# persephone_B_v1.net
KiCad netlist of a schematic drawn in EAGLE
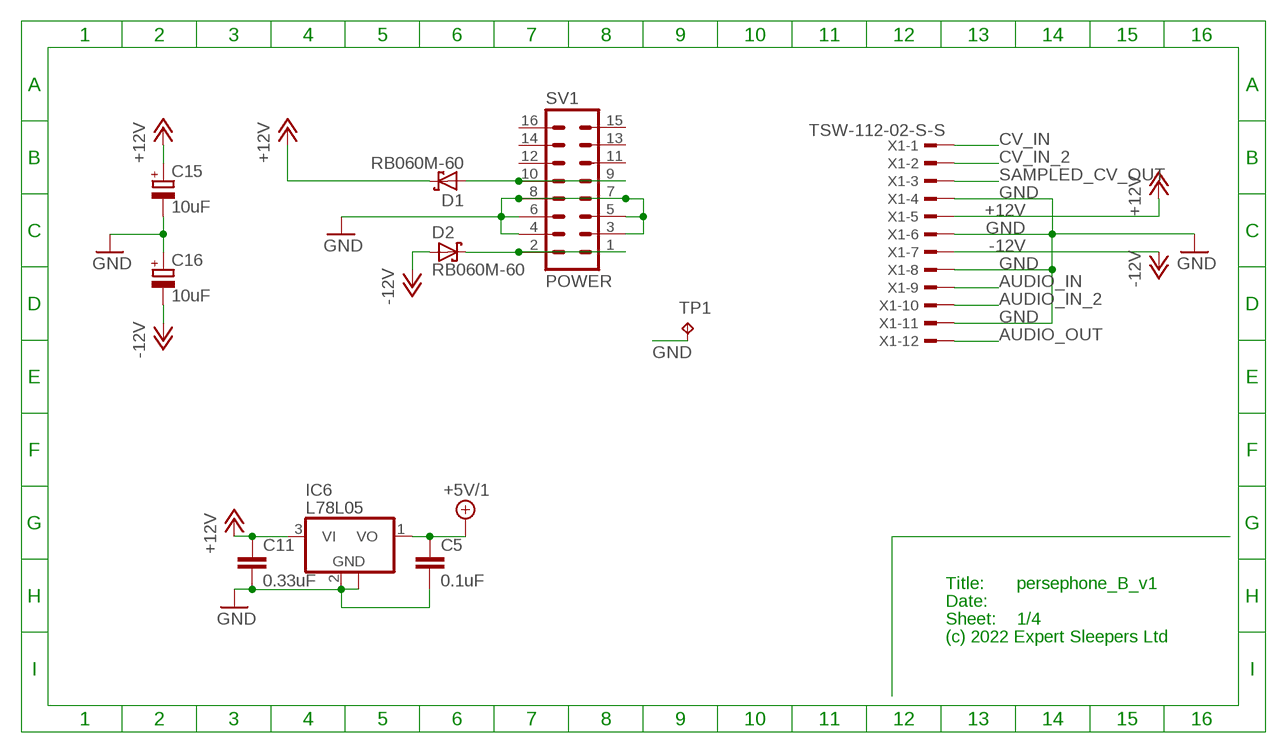
[diagram p0: schematic, sheet 1]
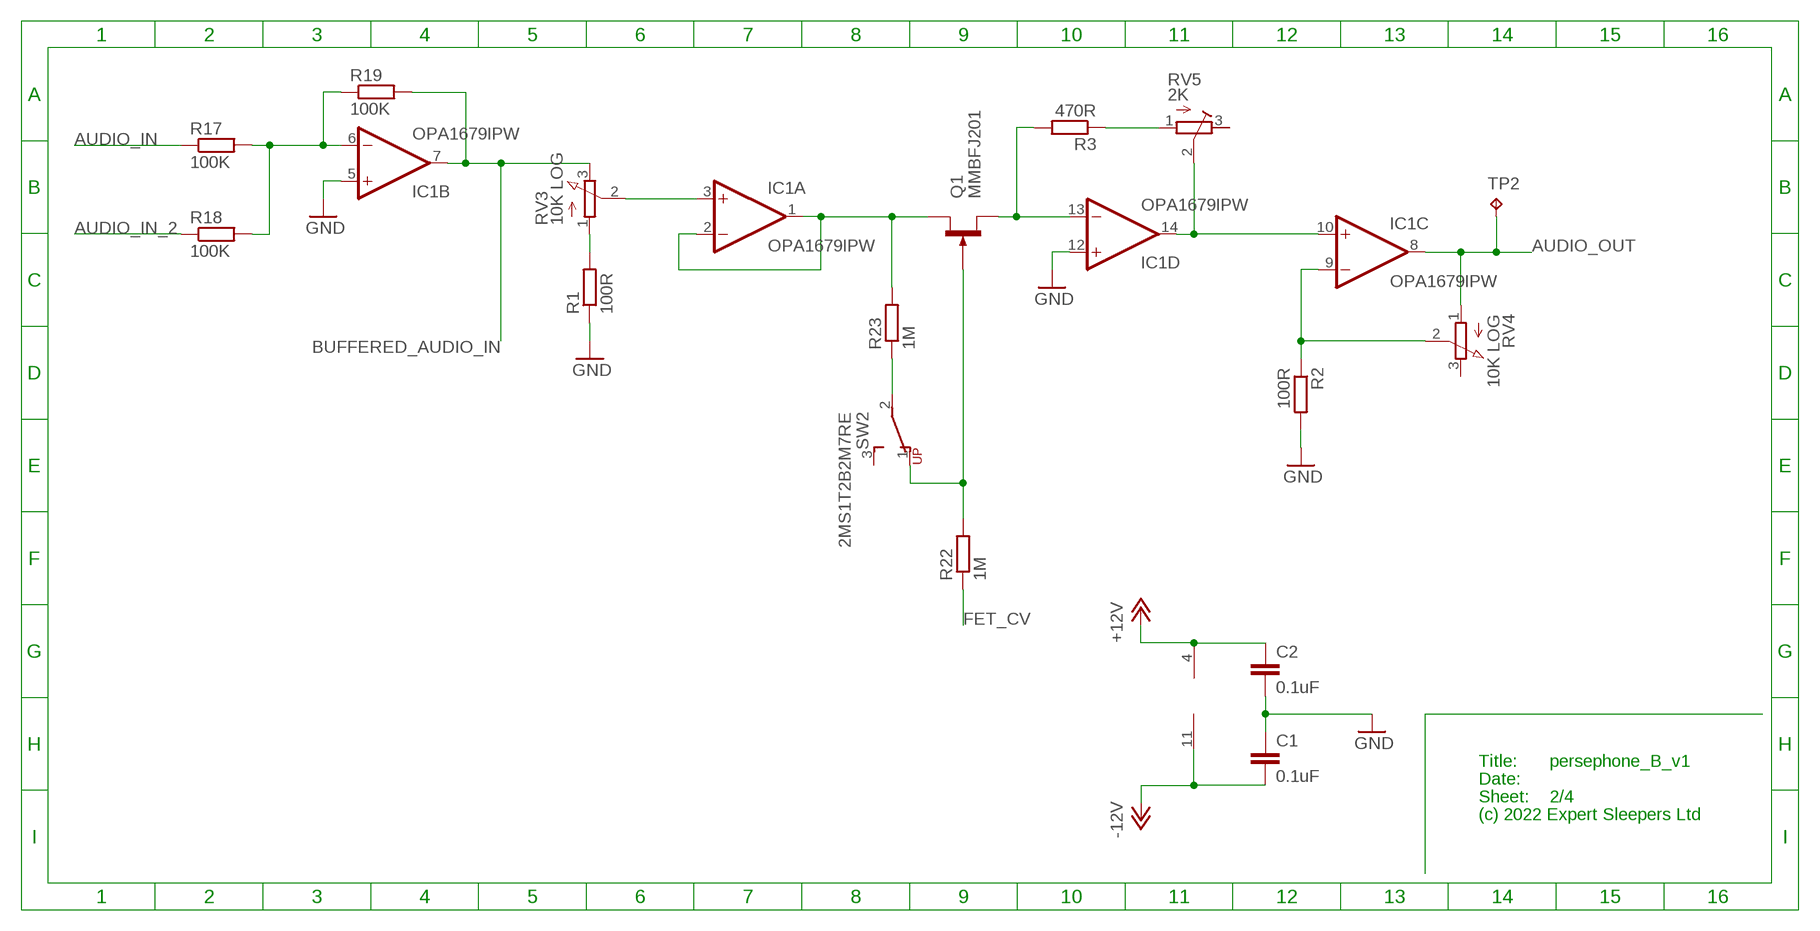
[diagram p1: schematic, sheet 2]
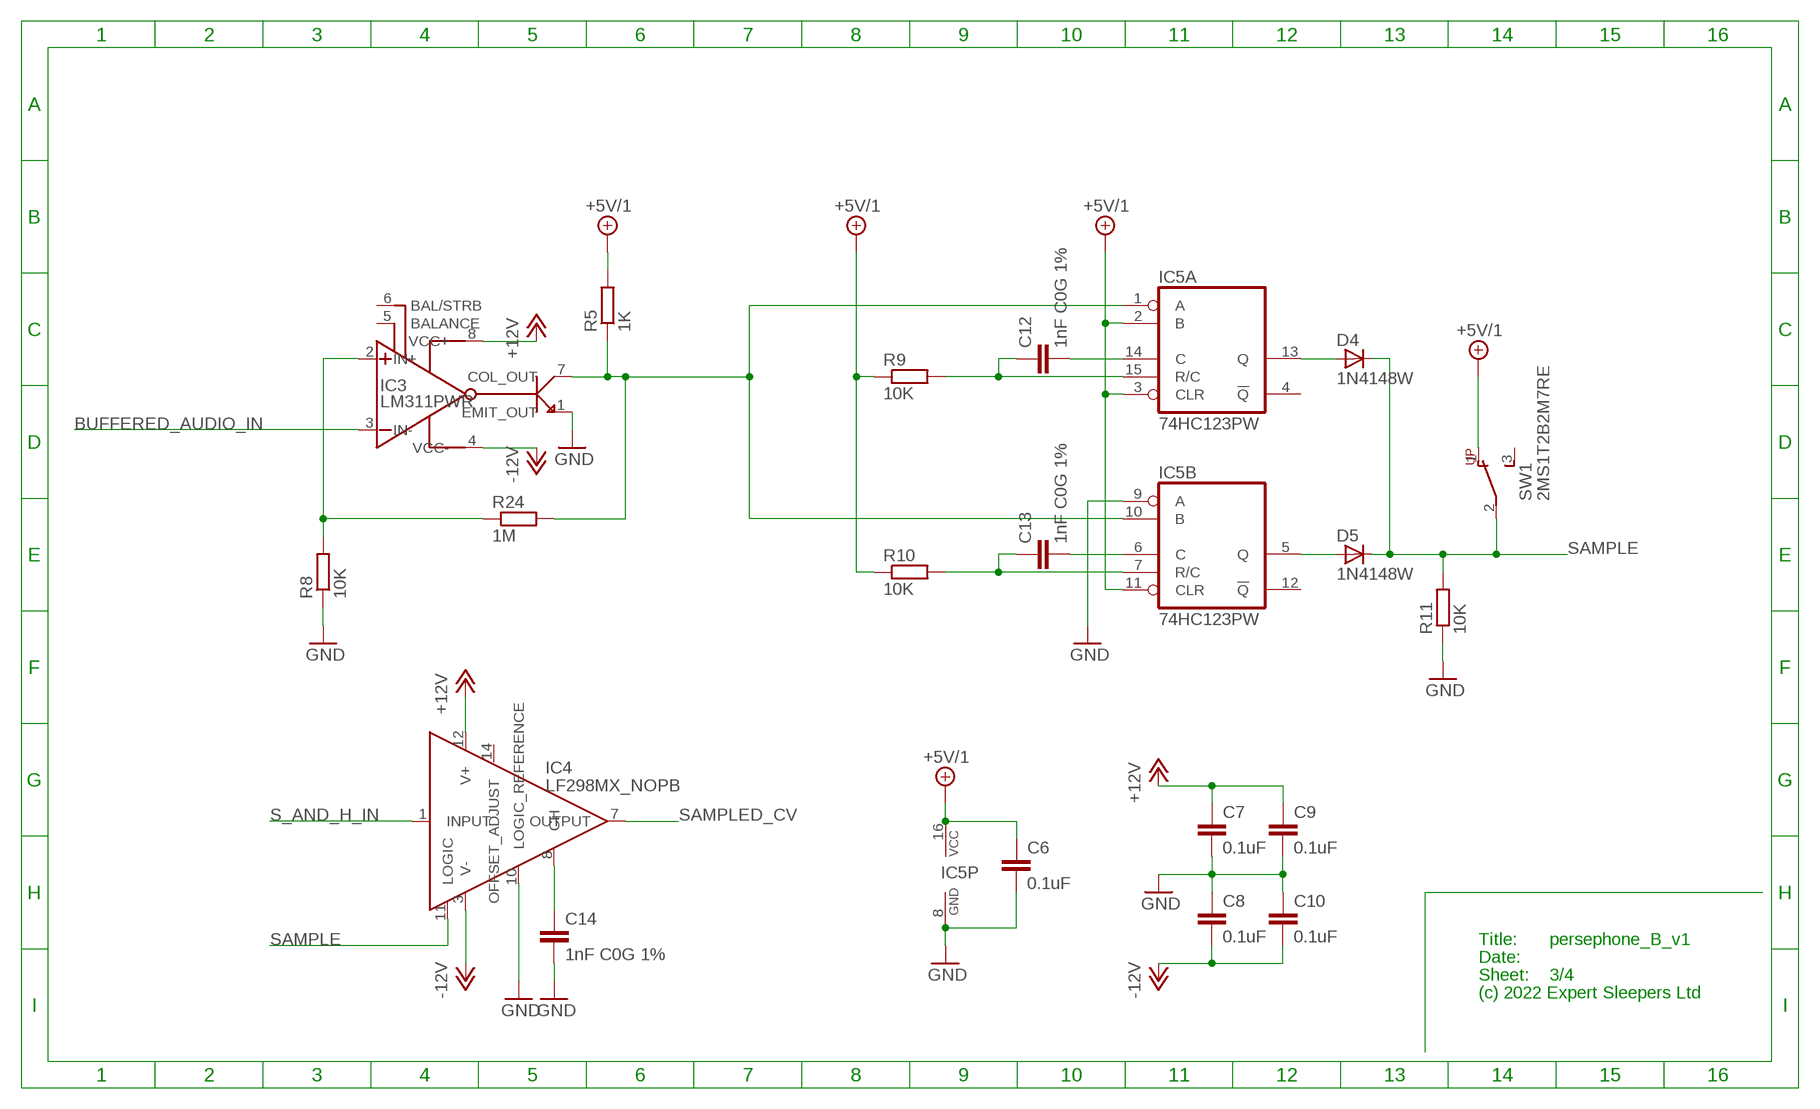
[diagram p2: schematic, sheet 3]
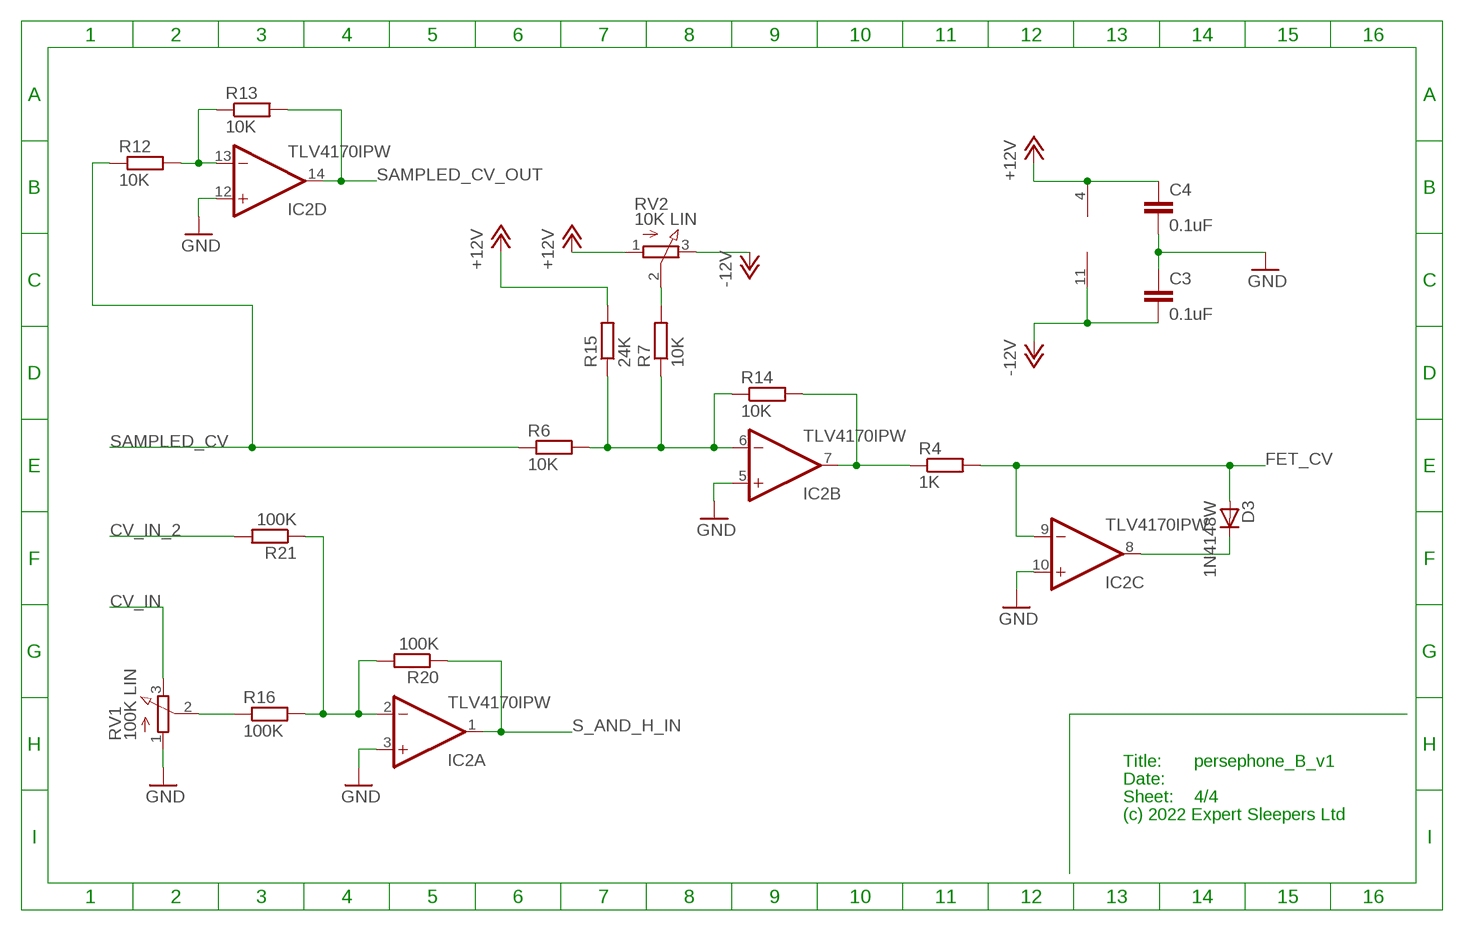
[diagram p3: schematic, sheet 4]

(export (version "E")
  (design (tool "Eeschema 10.0.6"))
  (components
    (comp (ref "C5")
      (value "0.1uF")
      (footprint "eagle-import:C0402")
      (libsource (lib "eagle-import") (part "C-EUC0402"))
    )
    (comp (ref "C11")
      (value "0.33uF")
      (footprint "eagle-import:C0805")
      (libsource (lib "eagle-import") (part "C-EUC0805"))
    )
    (comp (ref "C15")
      (value "10uF")
      (footprint "eagle-import:UD-4X5,8_NICHICON")
      (libsource (lib "eagle-import") (part "CPOL-EUUD-4X5,8"))
    )
    (comp (ref "C16")
      (value "10uF")
      (footprint "eagle-import:UD-4X5,8_NICHICON")
      (libsource (lib "eagle-import") (part "CPOL-EUUD-4X5,8"))
    )
    (comp (ref "D1")
      (value "RB060M-60")
      (footprint "eagle-import:SOD123FL")
      (libsource (lib "eagle-import") (part "RB060M-60"))
    )
    (comp (ref "D2")
      (value "RB060M-60")
      (footprint "eagle-import:SOD123FL")
      (libsource (lib "eagle-import") (part "RB060M-60"))
    )
    (comp (ref "IC6")
      (value "L78L05")
      (footprint "eagle-import:SOT89")
      (libsource (lib "eagle-import") (part "78LF05"))
    )
    (comp (ref "SV1")
      (value "POWER")
      (footprint "eagle-import:ML16")
      (libsource (lib "eagle-import") (part "ML16"))
    )
    (comp (ref "TP1")
      (value "RA2")
      (footprint "eagle-import:P1-13")
      (libsource (lib "eagle-import") (part "TPPAD1-13"))
    )
    (comp (ref "X1")
      (value "TSW-112-02-S-S")
      (footprint "eagle-import:TSW-112-02-S-S")
      (libsource (lib "eagle-import") (part "TSW-112-02-S-S"))
    )
    (comp (ref "C1")
      (value "0.1uF")
      (footprint "eagle-import:C0402")
      (libsource (lib "eagle-import") (part "C-EUC0402"))
    )
    (comp (ref "C2")
      (value "0.1uF")
      (footprint "eagle-import:C0402")
      (libsource (lib "eagle-import") (part "C-EUC0402"))
    )
    (comp (ref "IC1")
      (value "OPA1679IPW")
      (footprint "eagle-import:PW_R-PDSO-G14")
      (libsource (lib "eagle-import") (part "TL074PW"))
    )
    (comp (ref "Q1")
      (value "MMBFJ201")
      (footprint "eagle-import:SOT23")
      (libsource (lib "eagle-import") (part "MMBFJ3"))
    )
    (comp (ref "R1")
      (value "100R")
      (footprint "eagle-import:R0603")
      (libsource (lib "eagle-import") (part "R-EU_R0603"))
    )
    (comp (ref "R2")
      (value "100R")
      (footprint "eagle-import:R0603")
      (libsource (lib "eagle-import") (part "R-EU_R0603"))
    )
    (comp (ref "R3")
      (value "470R")
      (footprint "eagle-import:R0603")
      (libsource (lib "eagle-import") (part "R-EU_R0603"))
    )
    (comp (ref "R17")
      (value "100K")
      (footprint "eagle-import:R0603")
      (libsource (lib "eagle-import") (part "R-EU_R0603"))
    )
    (comp (ref "R18")
      (value "100K")
      (footprint "eagle-import:R0603")
      (libsource (lib "eagle-import") (part "R-EU_R0603"))
    )
    (comp (ref "R19")
      (value "100K")
      (footprint "eagle-import:R0603")
      (libsource (lib "eagle-import") (part "R-EU_R0603"))
    )
    (comp (ref "R22")
      (value "1M")
      (footprint "eagle-import:R0603")
      (libsource (lib "eagle-import") (part "R-EU_R0603"))
    )
    (comp (ref "R23")
      (value "1M")
      (footprint "eagle-import:R0603")
      (libsource (lib "eagle-import") (part "R-EU_R0603"))
    )
    (comp (ref "RV3")
      (value "10K LOG")
      (footprint "eagle-import:RD1610NOA0X")
      (libsource (lib "eagle-import") (part "RD1610NOA0X"))
    )
    (comp (ref "RV4")
      (value "10K LOG")
      (footprint "eagle-import:RD1610NOA0X")
      (libsource (lib "eagle-import") (part "RD1610NOA0X"))
    )
    (comp (ref "RV5")
      (value "2K")
      (footprint "eagle-import:TC33X")
      (libsource (lib "eagle-import") (part "TC33X"))
    )
    (comp (ref "SW2")
      (value "2MS1T2B2M7RE")
      (footprint "eagle-import:2MS1T2B2M7RE")
      (libsource (lib "eagle-import") (part "2MS1T2B2M7RE"))
    )
    (comp (ref "TP2")
      (value "RA2")
      (footprint "eagle-import:P1-13")
      (libsource (lib "eagle-import") (part "TPPAD1-13"))
    )
    (comp (ref "C6")
      (value "0.1uF")
      (footprint "eagle-import:C0402")
      (libsource (lib "eagle-import") (part "C-EUC0402"))
    )
    (comp (ref "C7")
      (value "0.1uF")
      (footprint "eagle-import:C0402")
      (libsource (lib "eagle-import") (part "C-EUC0402"))
    )
    (comp (ref "C8")
      (value "0.1uF")
      (footprint "eagle-import:C0402")
      (libsource (lib "eagle-import") (part "C-EUC0402"))
    )
    (comp (ref "C9")
      (value "0.1uF")
      (footprint "eagle-import:C0402")
      (libsource (lib "eagle-import") (part "C-EUC0402"))
    )
    (comp (ref "C10")
      (value "0.1uF")
      (footprint "eagle-import:C0402")
      (libsource (lib "eagle-import") (part "C-EUC0402"))
    )
    (comp (ref "C12")
      (value "1nF C0G 1%")
      (footprint "eagle-import:C0603")
      (libsource (lib "eagle-import") (part "C-EUC0603"))
    )
    (comp (ref "C13")
      (value "1nF C0G 1%")
      (footprint "eagle-import:C0603")
      (libsource (lib "eagle-import") (part "C-EUC0603"))
    )
    (comp (ref "C14")
      (value "1nF C0G 1%")
      (footprint "eagle-import:C0603")
      (libsource (lib "eagle-import") (part "C-EUC0603"))
    )
    (comp (ref "D4")
      (value "1N4148W")
      (footprint "eagle-import:SOD123")
      (libsource (lib "eagle-import") (part "D-SOD123"))
    )
    (comp (ref "D5")
      (value "1N4148W")
      (footprint "eagle-import:SOD123")
      (libsource (lib "eagle-import") (part "D-SOD123"))
    )
    (comp (ref "IC3")
      (value "LM311PWR")
      (footprint "eagle-import:SOP65P640X120-8N")
      (fields (field (name "MOUSER_PART_NUMBER") "595-LM311PWR"))
      (libsource (lib "eagle-import") (part "LM311PWR"))
    )
    (comp (ref "IC4")
      (value "LF298MX_NOPB")
      (footprint "eagle-import:SOIC127P600X175-14N")
      (fields
        (field (name "ARROW_PART_NUMBER") "LF298MX/NOPB")
        (field (name "MOUSER_PART_NUMBER") "926-LF298MX/NOPB")
      )
      (libsource (lib "eagle-import") (part "LF298MX_NOPB"))
    )
    (comp (ref "IC5")
      (value "74HC123PW")
      (footprint "eagle-import:PW_R-PDSO-G16")
      (libsource (lib "eagle-import") (part "74123PWHC"))
    )
    (comp (ref "R5")
      (value "1K")
      (footprint "eagle-import:R0603")
      (libsource (lib "eagle-import") (part "R-EU_R0603"))
    )
    (comp (ref "R8")
      (value "10K")
      (footprint "eagle-import:R0603")
      (libsource (lib "eagle-import") (part "R-EU_R0603"))
    )
    (comp (ref "R9")
      (value "10K")
      (footprint "eagle-import:R0603")
      (libsource (lib "eagle-import") (part "R-EU_R0603"))
    )
    (comp (ref "R10")
      (value "10K")
      (footprint "eagle-import:R0603")
      (libsource (lib "eagle-import") (part "R-EU_R0603"))
    )
    (comp (ref "R11")
      (value "10K")
      (footprint "eagle-import:R0603")
      (libsource (lib "eagle-import") (part "R-EU_R0603"))
    )
    (comp (ref "R24")
      (value "1M")
      (footprint "eagle-import:R0603")
      (libsource (lib "eagle-import") (part "R-EU_R0603"))
    )
    (comp (ref "SW1")
      (value "2MS1T2B2M7RE")
      (footprint "eagle-import:2MS1T2B2M7RE")
      (libsource (lib "eagle-import") (part "2MS1T2B2M7RE"))
    )
    (comp (ref "C3")
      (value "0.1uF")
      (footprint "eagle-import:C0402")
      (libsource (lib "eagle-import") (part "C-EUC0402"))
    )
    (comp (ref "C4")
      (value "0.1uF")
      (footprint "eagle-import:C0402")
      (libsource (lib "eagle-import") (part "C-EUC0402"))
    )
    (comp (ref "D3")
      (value "1N4148W")
      (footprint "eagle-import:SOD123")
      (libsource (lib "eagle-import") (part "D-SOD123"))
    )
    (comp (ref "IC2")
      (value "TLV4170IPW")
      (footprint "eagle-import:PW_R-PDSO-G14")
      (libsource (lib "eagle-import") (part "TL074PW"))
    )
    (comp (ref "R4")
      (value "1K")
      (footprint "eagle-import:R0603")
      (libsource (lib "eagle-import") (part "R-EU_R0603"))
    )
    (comp (ref "R6")
      (value "10K")
      (footprint "eagle-import:R0603")
      (libsource (lib "eagle-import") (part "R-EU_R0603"))
    )
    (comp (ref "R7")
      (value "10K")
      (footprint "eagle-import:R0603")
      (libsource (lib "eagle-import") (part "R-EU_R0603"))
    )
    (comp (ref "R12")
      (value "10K")
      (footprint "eagle-import:R0603")
      (libsource (lib "eagle-import") (part "R-EU_R0603"))
    )
    (comp (ref "R13")
      (value "10K")
      (footprint "eagle-import:R0603")
      (libsource (lib "eagle-import") (part "R-EU_R0603"))
    )
    (comp (ref "R14")
      (value "10K")
      (footprint "eagle-import:R0603")
      (libsource (lib "eagle-import") (part "R-EU_R0603"))
    )
    (comp (ref "R15")
      (value "24K")
      (footprint "eagle-import:R0603")
      (libsource (lib "eagle-import") (part "R-EU_R0603"))
    )
    (comp (ref "R16")
      (value "100K")
      (footprint "eagle-import:R0603")
      (libsource (lib "eagle-import") (part "R-EU_R0603"))
    )
    (comp (ref "R20")
      (value "100K")
      (footprint "eagle-import:R0603")
      (libsource (lib "eagle-import") (part "R-EU_R0603"))
    )
    (comp (ref "R21")
      (value "100K")
      (footprint "eagle-import:R0603")
      (libsource (lib "eagle-import") (part "R-EU_R0603"))
    )
    (comp (ref "RV1")
      (value "100K LIN")
      (footprint "eagle-import:RD1610NOA0X")
      (libsource (lib "eagle-import") (part "RD1610NOA0X"))
    )
    (comp (ref "RV2")
      (value "10K LIN")
      (footprint "eagle-import:RD1610NOA0X")
      (libsource (lib "eagle-import") (part "RD1610NOA0X"))
    )
  )
  (nets
    (net (code "1") (name "+5V{slash}1") (class "Default")
      (node (ref "C5") (pin "1") (pinfunction "1_1") (pintype "passive"))
      (node (ref "C6") (pin "1") (pinfunction "1_1") (pintype "passive"))
      (node (ref "IC5") (pin "11") (pinfunction "CLR_11") (pintype "input"))
      (node (ref "IC5") (pin "16") (pinfunction "VCC_16") (pintype "power_in"))
      (node (ref "IC5") (pin "2") (pinfunction "B_2") (pintype "input"))
      (node (ref "IC5") (pin "3") (pinfunction "CLR_3") (pintype "input"))
      (node (ref "IC6") (pin "1") (pinfunction "VO_1") (pintype "passive"))
      (node (ref "R10") (pin "1") (pinfunction "1_1") (pintype "passive"))
      (node (ref "R5") (pin "2") (pinfunction "2_2") (pintype "passive"))
      (node (ref "R9") (pin "1") (pinfunction "1_1") (pintype "passive"))
      (node (ref "SW1") (pin "1") (pinfunction "RU_1") (pintype "passive"))
    )
    (net (code "2") (name "+12V") (class "Default")
      (node (ref "C11") (pin "1") (pinfunction "1_1") (pintype "passive"))
      (node (ref "C15") (pin "+") (pinfunction "+_+") (pintype "passive"))
      (node (ref "C2") (pin "1") (pinfunction "1_1") (pintype "passive"))
      (node (ref "C4") (pin "1") (pinfunction "1_1") (pintype "passive"))
      (node (ref "C7") (pin "1") (pinfunction "1_1") (pintype "passive"))
      (node (ref "C9") (pin "1") (pinfunction "1_1") (pintype "passive"))
      (node (ref "D1") (pin "C") (pinfunction "C_C") (pintype "passive"))
      (node (ref "IC1") (pin "4") (pinfunction "V+_4") (pintype "power_in"))
      (node (ref "IC2") (pin "4") (pinfunction "V+_4") (pintype "power_in"))
      (node (ref "IC3") (pin "8") (pinfunction "VCC+_8") (pintype "power_in"))
      (node (ref "IC4") (pin "12") (pinfunction "V+_12") (pintype "power_in"))
      (node (ref "IC6") (pin "3") (pinfunction "VI_3") (pintype "input"))
      (node (ref "R15") (pin "2") (pinfunction "2_2") (pintype "passive"))
      (node (ref "RV2") (pin "1") (pinfunction "A_1") (pintype "passive"))
      (node (ref "X1") (pin "5") (pinfunction "1_5") (pintype "passive"))
    )
    (net (code "3") (name "-12V") (class "Default")
      (node (ref "C1") (pin "2") (pinfunction "2_2") (pintype "passive"))
      (node (ref "C10") (pin "2") (pinfunction "2_2") (pintype "passive"))
      (node (ref "C16") (pin "-") (pinfunction "-_-") (pintype "passive"))
      (node (ref "C3") (pin "2") (pinfunction "2_2") (pintype "passive"))
      (node (ref "C8") (pin "2") (pinfunction "2_2") (pintype "passive"))
      (node (ref "D2") (pin "A") (pinfunction "A_A") (pintype "passive"))
      (node (ref "IC1") (pin "11") (pinfunction "V-_11") (pintype "power_in"))
      (node (ref "IC2") (pin "11") (pinfunction "V-_11") (pintype "power_in"))
      (node (ref "IC3") (pin "4") (pinfunction "VCC-_4") (pintype "power_in"))
      (node (ref "IC4") (pin "3") (pinfunction "V-_3") (pintype "power_in"))
      (node (ref "RV2") (pin "3") (pinfunction "E_3") (pintype "passive"))
      (node (ref "X1") (pin "7") (pinfunction "1_7") (pintype "passive"))
    )
    (net (code "4") (name "AUDIO_IN") (class "Default")
      (node (ref "R17") (pin "1") (pinfunction "1_1") (pintype "passive"))
      (node (ref "X1") (pin "9") (pinfunction "1_9") (pintype "passive"))
    )
    (net (code "5") (name "AUDIO_IN_2") (class "Default")
      (node (ref "R18") (pin "1") (pinfunction "1_1") (pintype "passive"))
      (node (ref "X1") (pin "10") (pinfunction "1_10") (pintype "passive"))
    )
    (net (code "6") (name "AUDIO_OUT") (class "Default")
      (node (ref "IC1") (pin "8") (pinfunction "OUT_8") (pintype "output"))
      (node (ref "RV4") (pin "1") (pinfunction "A_1") (pintype "passive"))
      (node (ref "TP2") (pin "TP") (pinfunction "TP_TP") (pintype "input"))
      (node (ref "X1") (pin "12") (pinfunction "1_12") (pintype "passive"))
    )
    (net (code "7") (name "BUFFERED_AUDIO_IN") (class "Default")
      (node (ref "IC1") (pin "7") (pinfunction "OUT_7") (pintype "output"))
      (node (ref "IC3") (pin "3") (pinfunction "IN-_3") (pintype "input"))
      (node (ref "R19") (pin "2") (pinfunction "2_2") (pintype "passive"))
      (node (ref "RV3") (pin "3") (pinfunction "E_3") (pintype "passive"))
    )
    (net (code "8") (name "CV_IN") (class "Default")
      (node (ref "RV1") (pin "3") (pinfunction "E_3") (pintype "passive"))
      (node (ref "X1") (pin "1") (pinfunction "1_1") (pintype "passive"))
    )
    (net (code "9") (name "CV_IN_2") (class "Default")
      (node (ref "R21") (pin "2") (pinfunction "2_2") (pintype "passive"))
      (node (ref "X1") (pin "2") (pinfunction "1_2") (pintype "passive"))
    )
    (net (code "10") (name "FET_CV") (class "Default")
      (node (ref "D3") (pin "2") (pinfunction "A_2") (pintype "passive"))
      (node (ref "IC2") (pin "9") (pinfunction "-IN_9") (pintype "input"))
      (node (ref "R22") (pin "1") (pinfunction "1_1") (pintype "passive"))
      (node (ref "R4") (pin "2") (pinfunction "2_2") (pintype "passive"))
    )
    (net (code "11") (name "GND") (class "Default")
      (node (ref "C1") (pin "1") (pinfunction "1_1") (pintype "passive"))
      (node (ref "C10") (pin "1") (pinfunction "1_1") (pintype "passive"))
      (node (ref "C11") (pin "2") (pinfunction "2_2") (pintype "passive"))
      (node (ref "C14") (pin "2") (pinfunction "2_2") (pintype "passive"))
      (node (ref "C15") (pin "-") (pinfunction "-_-") (pintype "passive"))
      (node (ref "C16") (pin "+") (pinfunction "+_+") (pintype "passive"))
      (node (ref "C2") (pin "2") (pinfunction "2_2") (pintype "passive"))
      (node (ref "C3") (pin "1") (pinfunction "1_1") (pintype "passive"))
      (node (ref "C4") (pin "2") (pinfunction "2_2") (pintype "passive"))
      (node (ref "C5") (pin "2") (pinfunction "2_2") (pintype "passive"))
      (node (ref "C6") (pin "2") (pinfunction "2_2") (pintype "passive"))
      (node (ref "C7") (pin "2") (pinfunction "2_2") (pintype "passive"))
      (node (ref "C8") (pin "1") (pinfunction "1_1") (pintype "passive"))
      (node (ref "C9") (pin "2") (pinfunction "2_2") (pintype "passive"))
      (node (ref "IC1") (pin "12") (pinfunction "+IN_12") (pintype "input"))
      (node (ref "IC1") (pin "5") (pinfunction "+IN_5") (pintype "input"))
      (node (ref "IC2") (pin "10") (pinfunction "+IN_10") (pintype "input"))
      (node (ref "IC2") (pin "12") (pinfunction "+IN_12") (pintype "input"))
      (node (ref "IC2") (pin "3") (pinfunction "+IN_3") (pintype "input"))
      (node (ref "IC2") (pin "5") (pinfunction "+IN_5") (pintype "input"))
      (node (ref "IC3") (pin "1") (pinfunction "EMIT_OUT_1") (pintype "bidirectional"))
      (node (ref "IC4") (pin "10") (pinfunction "LOGIC_REFERENCE_10") (pintype "input"))
      (node (ref "IC5") (pin "8") (pinfunction "GND_8") (pintype "power_in"))
      (node (ref "IC5") (pin "9") (pinfunction "A_9") (pintype "input"))
      (node (ref "IC6") (pin "2") (pinfunction "GND_2") (pintype "passive"))
      (node (ref "IC6") (pin "2@1") (pinfunction "GND_2@1") (pintype "passive"))
      (node (ref "R1") (pin "1") (pinfunction "1_1") (pintype "passive"))
      (node (ref "R11") (pin "1") (pinfunction "1_1") (pintype "passive"))
      (node (ref "R2") (pin "2") (pinfunction "2_2") (pintype "passive"))
      (node (ref "R8") (pin "1") (pinfunction "1_1") (pintype "passive"))
      (node (ref "RV1") (pin "1") (pinfunction "A_1") (pintype "passive"))
      (node (ref "SV1") (pin "3") (pinfunction "3_3") (pintype "passive"))
      (node (ref "SV1") (pin "4") (pinfunction "4_4") (pintype "passive"))
      (node (ref "SV1") (pin "5") (pinfunction "5_5") (pintype "passive"))
      (node (ref "SV1") (pin "6") (pinfunction "6_6") (pintype "passive"))
      (node (ref "SV1") (pin "7") (pinfunction "7_7") (pintype "passive"))
      (node (ref "SV1") (pin "8") (pinfunction "8_8") (pintype "passive"))
      (node (ref "TP1") (pin "TP") (pinfunction "TP_TP") (pintype "input"))
      (node (ref "X1") (pin "11") (pinfunction "1_11") (pintype "passive"))
      (node (ref "X1") (pin "4") (pinfunction "1_4") (pintype "passive"))
      (node (ref "X1") (pin "6") (pinfunction "1_6") (pintype "passive"))
      (node (ref "X1") (pin "8") (pinfunction "1_8") (pintype "passive"))
    )
    (net (code "12") (name "Net-(D1-PadA)") (class "Default")
      (node (ref "D1") (pin "A") (pinfunction "A_A") (pintype "passive"))
      (node (ref "SV1") (pin "10") (pinfunction "10_10") (pintype "passive"))
      (node (ref "SV1") (pin "9") (pinfunction "9_9") (pintype "passive"))
    )
    (net (code "13") (name "Net-(D2-PadC)") (class "Default")
      (node (ref "D2") (pin "C") (pinfunction "C_C") (pintype "passive"))
      (node (ref "SV1") (pin "1") (pinfunction "1_1") (pintype "passive"))
      (node (ref "SV1") (pin "2") (pinfunction "2_2") (pintype "passive"))
    )
    (net (code "14") (name "Net-(D3-C)") (class "Default")
      (node (ref "D3") (pin "1") (pinfunction "C_1") (pintype "passive"))
      (node (ref "IC2") (pin "8") (pinfunction "OUT_8") (pintype "output"))
    )
    (net (code "15") (name "Net-(D4-A)") (class "Default")
      (node (ref "D4") (pin "2") (pinfunction "A_2") (pintype "passive"))
      (node (ref "IC5") (pin "13") (pinfunction "Q_13") (pintype "output"))
    )
    (net (code "16") (name "Net-(D5-A)") (class "Default")
      (node (ref "D5") (pin "2") (pinfunction "A_2") (pintype "passive"))
      (node (ref "IC5") (pin "5") (pinfunction "Q_5") (pintype "output"))
    )
    (net (code "17") (name "Net-(IC1A-+IN)") (class "Default")
      (node (ref "IC1") (pin "3") (pinfunction "+IN_3") (pintype "input"))
      (node (ref "RV3") (pin "2") (pinfunction "S_2") (pintype "passive"))
    )
    (net (code "18") (name "Net-(IC1A--IN)") (class "Default")
      (node (ref "IC1") (pin "1") (pinfunction "OUT_1") (pintype "output"))
      (node (ref "IC1") (pin "2") (pinfunction "-IN_2") (pintype "input"))
      (node (ref "Q1") (pin "1") (pinfunction "D_1") (pintype "passive"))
      (node (ref "R23") (pin "2") (pinfunction "2_2") (pintype "passive"))
    )
    (net (code "19") (name "Net-(IC1B--IN)") (class "Default")
      (node (ref "IC1") (pin "6") (pinfunction "-IN_6") (pintype "input"))
      (node (ref "R17") (pin "2") (pinfunction "2_2") (pintype "passive"))
      (node (ref "R18") (pin "2") (pinfunction "2_2") (pintype "passive"))
      (node (ref "R19") (pin "1") (pinfunction "1_1") (pintype "passive"))
    )
    (net (code "20") (name "Net-(IC1C-+IN)") (class "Default")
      (node (ref "IC1") (pin "10") (pinfunction "+IN_10") (pintype "input"))
      (node (ref "IC1") (pin "14") (pinfunction "OUT_14") (pintype "output"))
      (node (ref "RV5") (pin "2") (pinfunction "S_2") (pintype "passive"))
    )
    (net (code "21") (name "Net-(IC1C--IN)") (class "Default")
      (node (ref "IC1") (pin "9") (pinfunction "-IN_9") (pintype "input"))
      (node (ref "R2") (pin "1") (pinfunction "1_1") (pintype "passive"))
      (node (ref "RV4") (pin "2") (pinfunction "S_2") (pintype "passive"))
    )
    (net (code "22") (name "Net-(IC1D--IN)") (class "Default")
      (node (ref "IC1") (pin "13") (pinfunction "-IN_13") (pintype "input"))
      (node (ref "Q1") (pin "2") (pinfunction "S_2") (pintype "passive"))
      (node (ref "R3") (pin "2") (pinfunction "2_2") (pintype "passive"))
    )
    (net (code "23") (name "Net-(IC2A--IN)") (class "Default")
      (node (ref "IC2") (pin "2") (pinfunction "-IN_2") (pintype "input"))
      (node (ref "R16") (pin "2") (pinfunction "2_2") (pintype "passive"))
      (node (ref "R20") (pin "2") (pinfunction "2_2") (pintype "passive"))
      (node (ref "R21") (pin "1") (pinfunction "1_1") (pintype "passive"))
    )
    (net (code "24") (name "Net-(IC2B--IN)") (class "Default")
      (node (ref "IC2") (pin "6") (pinfunction "-IN_6") (pintype "input"))
      (node (ref "R14") (pin "1") (pinfunction "1_1") (pintype "passive"))
      (node (ref "R15") (pin "1") (pinfunction "1_1") (pintype "passive"))
      (node (ref "R6") (pin "2") (pinfunction "2_2") (pintype "passive"))
      (node (ref "R7") (pin "1") (pinfunction "1_1") (pintype "passive"))
    )
    (net (code "25") (name "Net-(IC2B-OUT)") (class "Default")
      (node (ref "IC2") (pin "7") (pinfunction "OUT_7") (pintype "output"))
      (node (ref "R14") (pin "2") (pinfunction "2_2") (pintype "passive"))
      (node (ref "R4") (pin "1") (pinfunction "1_1") (pintype "passive"))
    )
    (net (code "26") (name "Net-(IC2D--IN)") (class "Default")
      (node (ref "IC2") (pin "13") (pinfunction "-IN_13") (pintype "input"))
      (node (ref "R12") (pin "2") (pinfunction "2_2") (pintype "passive"))
      (node (ref "R13") (pin "1") (pinfunction "1_1") (pintype "passive"))
    )
    (net (code "27") (name "Net-(IC3-COL_OUT)") (class "Default")
      (node (ref "IC3") (pin "7") (pinfunction "COL_OUT_7") (pintype "bidirectional"))
      (node (ref "IC5") (pin "1") (pinfunction "A_1") (pintype "input"))
      (node (ref "IC5") (pin "10") (pinfunction "B_10") (pintype "input"))
      (node (ref "R24") (pin "2") (pinfunction "2_2") (pintype "passive"))
      (node (ref "R5") (pin "1") (pinfunction "1_1") (pintype "passive"))
    )
    (net (code "28") (name "Net-(IC3-IN+)") (class "Default")
      (node (ref "IC3") (pin "2") (pinfunction "IN+_2") (pintype "input"))
      (node (ref "R24") (pin "1") (pinfunction "1_1") (pintype "passive"))
      (node (ref "R8") (pin "2") (pinfunction "2_2") (pintype "passive"))
    )
    (net (code "29") (name "Net-(IC4-CH)") (class "Default")
      (node (ref "C14") (pin "1") (pinfunction "1_1") (pintype "passive"))
      (node (ref "IC4") (pin "8") (pinfunction "CH_8") (pintype "bidirectional"))
    )
    (net (code "30") (name "Net-(IC5A-C)") (class "Default")
      (node (ref "C12") (pin "2") (pinfunction "2_2") (pintype "passive"))
      (node (ref "IC5") (pin "14") (pinfunction "C_14") (pintype "input"))
    )
    (net (code "31") (name "Net-(IC5A-R{slash}C)") (class "Default")
      (node (ref "C12") (pin "1") (pinfunction "1_1") (pintype "passive"))
      (node (ref "IC5") (pin "15") (pinfunction "R/C_15") (pintype "input"))
      (node (ref "R9") (pin "2") (pinfunction "2_2") (pintype "passive"))
    )
    (net (code "32") (name "Net-(IC5B-C)") (class "Default")
      (node (ref "C13") (pin "2") (pinfunction "2_2") (pintype "passive"))
      (node (ref "IC5") (pin "6") (pinfunction "C_6") (pintype "input"))
    )
    (net (code "33") (name "Net-(IC5B-R{slash}C)") (class "Default")
      (node (ref "C13") (pin "1") (pinfunction "1_1") (pintype "passive"))
      (node (ref "IC5") (pin "7") (pinfunction "R/C_7") (pintype "input"))
      (node (ref "R10") (pin "2") (pinfunction "2_2") (pintype "passive"))
    )
    (net (code "34") (name "Net-(Q1-G)") (class "Default")
      (node (ref "Q1") (pin "3") (pinfunction "G_3") (pintype "passive"))
      (node (ref "R22") (pin "2") (pinfunction "2_2") (pintype "passive"))
      (node (ref "SW2") (pin "1") (pinfunction "RU_1") (pintype "passive"))
    )
    (net (code "35") (name "Net-(RV1-S)") (class "Default")
      (node (ref "R16") (pin "1") (pinfunction "1_1") (pintype "passive"))
      (node (ref "RV1") (pin "2") (pinfunction "S_2") (pintype "passive"))
    )
    (net (code "36") (name "Net-(RV2-S)") (class "Default")
      (node (ref "R7") (pin "2") (pinfunction "2_2") (pintype "passive"))
      (node (ref "RV2") (pin "2") (pinfunction "S_2") (pintype "passive"))
    )
    (net (code "37") (name "Net-(RV3-A)") (class "Default")
      (node (ref "R1") (pin "2") (pinfunction "2_2") (pintype "passive"))
      (node (ref "RV3") (pin "1") (pinfunction "A_1") (pintype "passive"))
    )
    (net (code "38") (name "Net-(RV5-A)") (class "Default")
      (node (ref "R3") (pin "1") (pinfunction "1_1") (pintype "passive"))
      (node (ref "RV5") (pin "1") (pinfunction "A_1") (pintype "passive"))
    )
    (net (code "39") (name "Net-(SW2-PR)") (class "Default")
      (node (ref "R23") (pin "1") (pinfunction "1_1") (pintype "passive"))
      (node (ref "SW2") (pin "2") (pinfunction "PR_2") (pintype "passive"))
    )
    (net (code "40") (name "SAMPLE") (class "Default")
      (node (ref "D4") (pin "1") (pinfunction "C_1") (pintype "passive"))
      (node (ref "D5") (pin "1") (pinfunction "C_1") (pintype "passive"))
      (node (ref "IC4") (pin "11") (pinfunction "LOGIC_11") (pintype "input"))
      (node (ref "R11") (pin "2") (pinfunction "2_2") (pintype "passive"))
      (node (ref "SW1") (pin "2") (pinfunction "PR_2") (pintype "passive"))
    )
    (net (code "41") (name "SAMPLED_CV") (class "Default")
      (node (ref "IC4") (pin "7") (pinfunction "OUTPUT_7") (pintype "output"))
      (node (ref "R12") (pin "1") (pinfunction "1_1") (pintype "passive"))
      (node (ref "R6") (pin "1") (pinfunction "1_1") (pintype "passive"))
    )
    (net (code "42") (name "SAMPLED_CV_OUT") (class "Default")
      (node (ref "IC2") (pin "14") (pinfunction "OUT_14") (pintype "output"))
      (node (ref "R13") (pin "2") (pinfunction "2_2") (pintype "passive"))
      (node (ref "X1") (pin "3") (pinfunction "1_3") (pintype "passive"))
    )
    (net (code "43") (name "S_AND_H_IN") (class "Default")
      (node (ref "IC2") (pin "1") (pinfunction "OUT_1") (pintype "output"))
      (node (ref "IC4") (pin "1") (pinfunction "INPUT_1") (pintype "input"))
      (node (ref "R20") (pin "1") (pinfunction "1_1") (pintype "passive"))
    )
    (net (code "44") (name "unconnected-(IC3-BALANCE-Pad5)") (class "Default")
      (node (ref "IC3") (pin "5") (pinfunction "BALANCE_5") (pintype "bidirectional"))
    )
    (net (code "45") (name "unconnected-(IC3-BAL{slash}STRB-Pad6)") (class "Default")
      (node (ref "IC3") (pin "6") (pinfunction "BAL/STRB_6") (pintype "bidirectional"))
    )
    (net (code "46") (name "unconnected-(IC4-OFFSET_ADJUST-Pad14)") (class "Default")
      (node (ref "IC4") (pin "14") (pinfunction "OFFSET_ADJUST_14") (pintype "input"))
    )
    (net (code "47") (name "unconnected-(IC5A-~{Q}-Pad4)") (class "Default")
      (node (ref "IC5") (pin "4") (pinfunction "~{Q}_4") (pintype "output"))
    )
    (net (code "48") (name "unconnected-(IC5B-~{Q}-Pad12)") (class "Default")
      (node (ref "IC5") (pin "12") (pinfunction "~{Q}_12") (pintype "output"))
    )
    (net (code "49") (name "unconnected-(RV4-E-Pad3)") (class "Default")
      (node (ref "RV4") (pin "3") (pinfunction "E_3") (pintype "passive"))
    )
    (net (code "50") (name "unconnected-(RV5-E-Pad3)") (class "Default")
      (node (ref "RV5") (pin "3") (pinfunction "E_3") (pintype "passive"))
    )
    (net (code "51") (name "unconnected-(SV1-Pad11)") (class "Default")
      (node (ref "SV1") (pin "11") (pinfunction "11_11") (pintype "passive"))
    )
    (net (code "52") (name "unconnected-(SV1-Pad12)") (class "Default")
      (node (ref "SV1") (pin "12") (pinfunction "12_12") (pintype "passive"))
    )
    (net (code "53") (name "unconnected-(SV1-Pad13)") (class "Default")
      (node (ref "SV1") (pin "13") (pinfunction "13_13") (pintype "passive"))
    )
    (net (code "54") (name "unconnected-(SV1-Pad14)") (class "Default")
      (node (ref "SV1") (pin "14") (pinfunction "14_14") (pintype "passive"))
    )
    (net (code "55") (name "unconnected-(SV1-Pad15)") (class "Default")
      (node (ref "SV1") (pin "15") (pinfunction "15_15") (pintype "passive"))
    )
    (net (code "56") (name "unconnected-(SV1-Pad16)") (class "Default")
      (node (ref "SV1") (pin "16") (pinfunction "16_16") (pintype "passive"))
    )
    (net (code "57") (name "unconnected-(SW1-RD-Pad3)") (class "Default")
      (node (ref "SW1") (pin "3") (pinfunction "RD_3") (pintype "passive"))
    )
    (net (code "58") (name "unconnected-(SW2-RD-Pad3)") (class "Default")
      (node (ref "SW2") (pin "3") (pinfunction "RD_3") (pintype "passive"))
    )
  )
)
